# PICHeaderBoard.net
KiCad netlist of a schematic drawn in Altium Designer
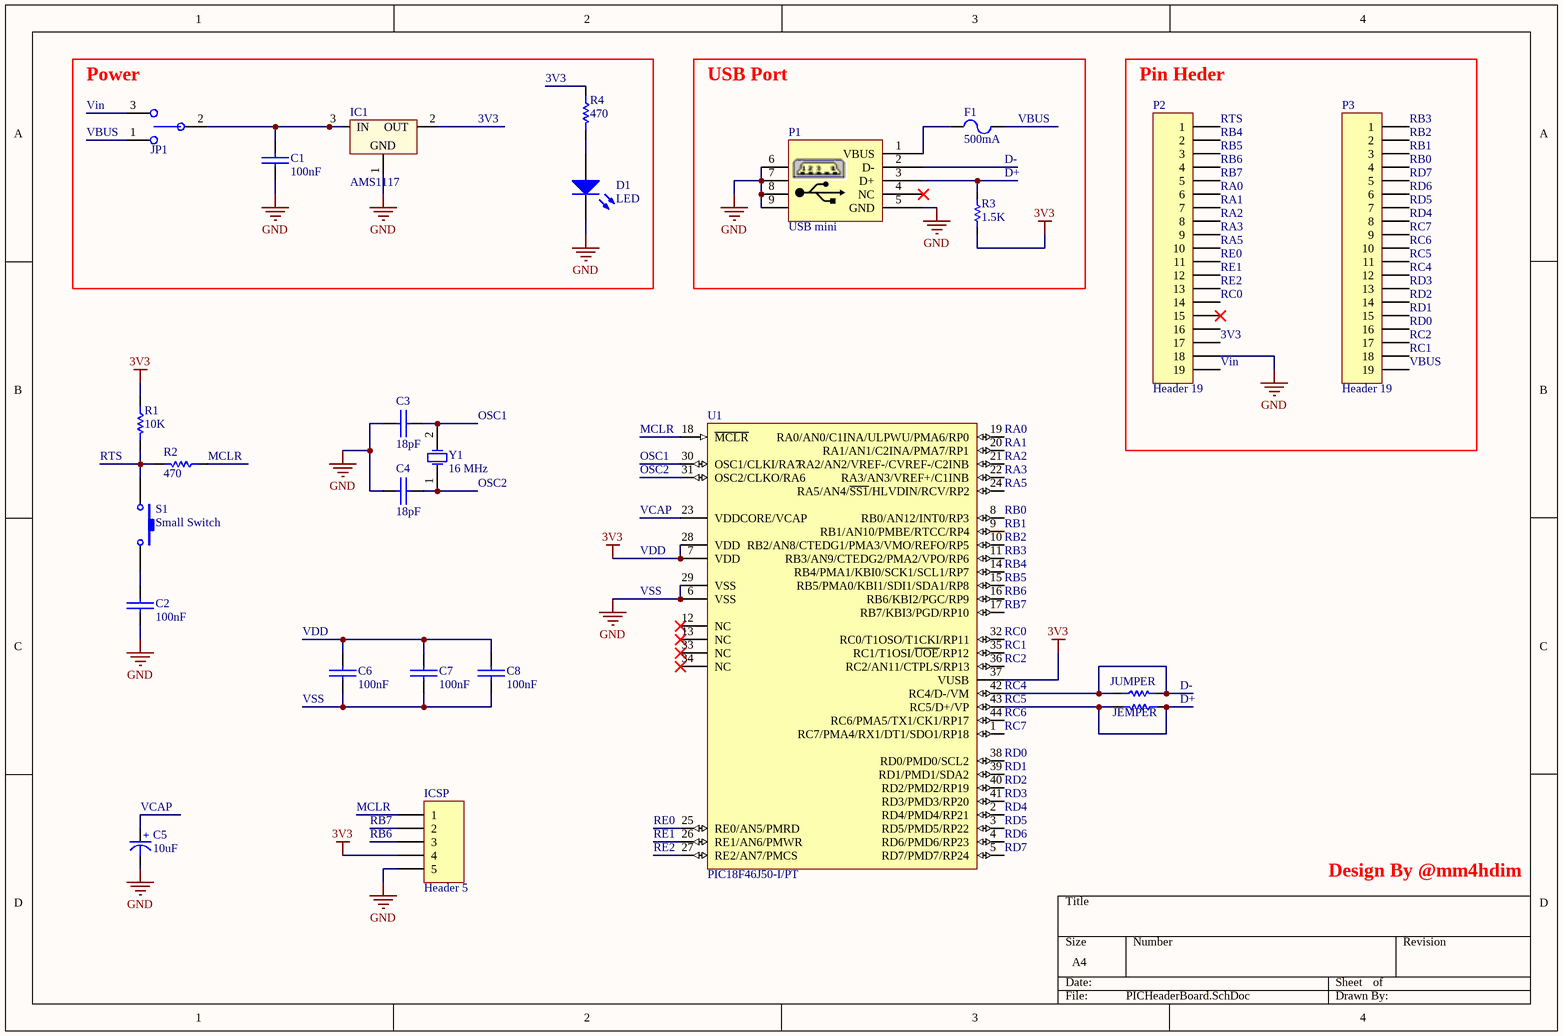
[diagram p0: PICHeaderBoard.SchDoc]

(export (version "E")
  (design (tool "Eeschema 10.0.6"))
  (components
    (comp (ref "C1")
      (value "100nF")
      (footprint "SMD_CAP_0805")
      (description "Bipolar Capacitor")
      (fields (field (name "VOLTAGE") "100V") (field (name "DESIGNER") "Saeid Jorablo"))
      (libsource (lib "My_Library") (part "Cap-Bipolar"))
    )
    (comp (ref "C2")
      (value "100nF")
      (footprint "SMD_CAP_0805")
      (description "Bipolar Capacitor")
      (fields (field (name "VOLTAGE") "100V") (field (name "DESIGNER") "Saeid Jorablo"))
      (libsource (lib "My_Library") (part "Cap-Bipolar"))
    )
    (comp (ref "C3")
      (value "18pF")
      (footprint "SMD_CAP_0805")
      (description "Bipolar Capacitor")
      (fields (field (name "VOLTAGE") "100V") (field (name "DESIGNER") "Saeid Jorablo"))
      (libsource (lib "My_Library") (part "Cap-Bipolar"))
    )
    (comp (ref "C4")
      (value "18pF")
      (footprint "SMD_CAP_0805")
      (description "Bipolar Capacitor")
      (fields (field (name "VOLTAGE") "100V") (field (name "DESIGNER") "Saeid Jorablo"))
      (libsource (lib "My_Library") (part "Cap-Bipolar"))
    )
    (comp (ref "C5")
      (value "10uF")
      (footprint "TANTAL-CAP-Size A")
      (description "Electrolytic Capacitor")
      (libsource (lib "AltiumLib1") (part "Capacitor Electrolytic"))
    )
    (comp (ref "C6")
      (value "100nF")
      (footprint "SMD_CAP_0805")
      (description "Bipolar Capacitor")
      (fields (field (name "VOLTAGE") "100V") (field (name "DESIGNER") "Saeid Jorablo"))
      (libsource (lib "My_Library") (part "Cap-Bipolar"))
    )
    (comp (ref "C7")
      (value "100nF")
      (footprint "SMD_CAP_0805")
      (description "Bipolar Capacitor")
      (fields (field (name "VOLTAGE") "100V") (field (name "DESIGNER") "Saeid Jorablo"))
      (libsource (lib "My_Library") (part "Cap-Bipolar"))
    )
    (comp (ref "C8")
      (value "100nF")
      (footprint "SMD_CAP_0805")
      (description "Bipolar Capacitor")
      (fields (field (name "VOLTAGE") "100V") (field (name "DESIGNER") "Saeid Jorablo"))
      (libsource (lib "My_Library") (part "Cap-Bipolar"))
    )
    (comp (ref "D1")
      (value "LED")
      (footprint "LED")
      (fields (field (name "PUBLISHER") "Altium Limited"))
      (libsource (lib "My Library") (part "LED"))
    )
    (comp (ref "F1")
      (value "500mA")
      (footprint "SMD_RES_1206")
      (description "Fuse")
      (libsource (lib "AltiumLib1") (part "Fuse"))
    )
    (comp (ref "IC1") (value "AMS1117") (footprint "SOT223") (libsource (lib "My Library") (part "AMS1117")))
    (comp (ref "ICSP")
      (value "Header 5")
      (footprint "HDR1X5")
      (description "Header, 5-Pin")
      (fields (field (name "PUBLISHER") "Altium Limited"))
      (libsource (lib "Miscellaneous Connectors") (part "Header 5"))
    )
    (comp (ref "J1")
      (value "JUMPER")
      (footprint "SMD_RES_0603")
      (description "Resistor")
      (fields (field (name "TOLERANCE") "5%") (field (name "POWER") "1/8 W"))
      (libsource (lib "My_Library") (part "Resistor"))
    )
    (comp (ref "J2")
      (value "JEMPER")
      (footprint "SMD_RES_0603")
      (description "Resistor")
      (fields (field (name "TOLERANCE") "5%") (field (name "POWER") "1/8 W"))
      (libsource (lib "My_Library") (part "Resistor"))
    )
    (comp (ref "JP1")
      (value "Jumper Selector")
      (footprint "Jumper Selector")
      (libsource (lib "AltiumLib1") (part "Jumper Selector"))
    )
    (comp (ref "P1")
      (value "USB mini")
      (footprint "USB/SM0.8-6H5")
      (description "mini USB Connector")
      (libsource (lib "My_Library") (part "USB mini"))
    )
    (comp (ref "P2")
      (value "Header 19")
      (footprint "HDR1X19")
      (description "Header, 19-Pin")
      (fields (field (name "PUBLISHER") "Altium Limited"))
      (libsource (lib "Miscellaneous Connectors") (part "Header 19"))
    )
    (comp (ref "P3")
      (value "Header 19")
      (footprint "HDR1X19")
      (description "Header, 19-Pin")
      (fields (field (name "PUBLISHER") "Altium Limited"))
      (libsource (lib "Miscellaneous Connectors") (part "Header 19"))
    )
    (comp (ref "R1")
      (value "10K")
      (footprint "SMD_RES_0805")
      (description "Resistor")
      (fields (field (name "TOLERANCE") "5%") (field (name "POWER") "1/8 W"))
      (libsource (lib "My_Library") (part "Resistor"))
    )
    (comp (ref "R2")
      (value "470")
      (footprint "SMD_RES_0805")
      (description "Resistor")
      (fields (field (name "TOLERANCE") "5%") (field (name "POWER") "1/8 W"))
      (libsource (lib "My_Library") (part "Resistor"))
    )
    (comp (ref "R3")
      (value "1.5K")
      (footprint "SMD_RES_0805")
      (description "Resistor")
      (fields (field (name "TOLERANCE") "5%") (field (name "POWER") "1/4 W"))
      (libsource (lib "AltiumLib1") (part "Resistor"))
    )
    (comp (ref "R4")
      (value "470")
      (footprint "SMD_RES_0805")
      (description "Resistor")
      (fields (field (name "TOLERANCE") "5%") (field (name "POWER") "1/8 W"))
      (libsource (lib "My_Library") (part "Resistor"))
    )
    (comp (ref "S1")
      (value "Small Switch")
      (footprint "Small Switch")
      (libsource (lib "My Library") (part "Small Switch"))
    )
    (comp (ref "U1")
      (value "PIC18F46J50-I/PT")
      (footprint "TQFP-PT44_N")
      (fields (field (name "PUBLISHER") "Altium Limited"))
      (libsource (lib "Microchip Microcontroller 8-Bit PIC18") (part "PIC18F46J50-I/PT"))
    )
    (comp (ref "Y1")
      (value "16 MHz")
      (footprint "XTAL Small")
      (description "XTAL Crystal")
      (libsource (lib "My_Library") (part "XTAL"))
    )
  )
  (nets
    (net (code "1") (name "/D+") (class "Default")
      (node (ref "J2") (pin "1") (pinfunction "1_1") (pintype "passive"))
      (node (ref "J2") (pin "2") (pinfunction "2_2") (pintype "passive"))
      (node (ref "P1") (pin "3") (pinfunction "D+_3") (pintype "passive"))
      (node (ref "P3") (pin "11") (pinfunction "11_11") (pintype "passive"))
      (node (ref "R3") (pin "2") (pinfunction "2_2") (pintype "passive"))
      (node (ref "U1") (pin "43") (pinfunction "RC5/D+/VP_43") (pintype "bidirectional"))
    )
    (net (code "2") (name "/D-") (class "Default")
      (node (ref "J1") (pin "1") (pinfunction "1_1") (pintype "passive"))
      (node (ref "J1") (pin "2") (pinfunction "2_2") (pintype "passive"))
      (node (ref "P1") (pin "2") (pinfunction "D-_2") (pintype "passive"))
      (node (ref "P3") (pin "12") (pinfunction "12_12") (pintype "passive"))
      (node (ref "U1") (pin "42") (pinfunction "RC4/D-/VM_42") (pintype "bidirectional"))
    )
    (net (code "3") (name "/MCLR") (class "Default")
      (node (ref "ICSP") (pin "1") (pinfunction "1_1") (pintype "passive"))
      (node (ref "R2") (pin "1") (pinfunction "1_1") (pintype "passive"))
      (node (ref "U1") (pin "18") (pinfunction "~{MCLR}_18") (pintype "input"))
    )
    (net (code "4") (name "/OSC1") (class "Default")
      (node (ref "C3") (pin "2") (pinfunction "-_2") (pintype "passive"))
      (node (ref "U1") (pin "30") (pinfunction "OSC1/CLKI/RA7_30") (pintype "bidirectional"))
      (node (ref "Y1") (pin "2") (pinfunction "OSC2_2") (pintype "passive"))
    )
    (net (code "5") (name "/OSC2") (class "Default")
      (node (ref "C4") (pin "2") (pinfunction "-_2") (pintype "passive"))
      (node (ref "U1") (pin "31") (pinfunction "OSC2/CLKO/RA6_31") (pintype "bidirectional"))
      (node (ref "Y1") (pin "1") (pinfunction "OSC1_1") (pintype "passive"))
    )
    (net (code "6") (name "/RA0") (class "Default")
      (node (ref "P2") (pin "6") (pinfunction "6_6") (pintype "passive"))
      (node (ref "U1") (pin "19") (pinfunction "RA0/AN0/C1INA/ULPWU/PMA6/RP0_19") (pintype "bidirectional"))
    )
    (net (code "7") (name "/RA1") (class "Default")
      (node (ref "P2") (pin "7") (pinfunction "7_7") (pintype "passive"))
      (node (ref "U1") (pin "20") (pinfunction "RA1/AN1/C2INA/PMA7/RP1_20") (pintype "bidirectional"))
    )
    (net (code "8") (name "/RA2") (class "Default")
      (node (ref "P2") (pin "8") (pinfunction "8_8") (pintype "passive"))
      (node (ref "U1") (pin "21") (pinfunction "RA2/AN2/VREF-/CVREF-/C2INB_21") (pintype "bidirectional"))
    )
    (net (code "9") (name "/RA3") (class "Default")
      (node (ref "P2") (pin "9") (pinfunction "9_9") (pintype "passive"))
      (node (ref "U1") (pin "22") (pinfunction "RA3/AN3/VREF+/C1INB_22") (pintype "bidirectional"))
    )
    (net (code "10") (name "/RA5") (class "Default")
      (node (ref "P2") (pin "10") (pinfunction "10_10") (pintype "passive"))
      (node (ref "U1") (pin "24") (pinfunction "RA5/AN4/~{SS1}/HLVDIN/RCV/RP2_24") (pintype "bidirectional"))
    )
    (net (code "11") (name "/RB0") (class "Default")
      (node (ref "P3") (pin "4") (pinfunction "4_4") (pintype "passive"))
      (node (ref "U1") (pin "8") (pinfunction "RB0/AN12/INT0/RP3_8") (pintype "bidirectional"))
    )
    (net (code "12") (name "/RB1") (class "Default")
      (node (ref "P3") (pin "3") (pinfunction "3_3") (pintype "passive"))
      (node (ref "U1") (pin "9") (pinfunction "RB1/AN10/PMBE/RTCC/RP4_9") (pintype "bidirectional"))
    )
    (net (code "13") (name "/RB2") (class "Default")
      (node (ref "P3") (pin "2") (pinfunction "2_2") (pintype "passive"))
      (node (ref "U1") (pin "10") (pinfunction "RB2/AN8/CTEDG1/PMA3/VMO/REFO/RP5_10") (pintype "bidirectional"))
    )
    (net (code "14") (name "/RB3") (class "Default")
      (node (ref "P3") (pin "1") (pinfunction "1_1") (pintype "passive"))
      (node (ref "U1") (pin "11") (pinfunction "RB3/AN9/CTEDG2/PMA2/VPO/RP6_11") (pintype "bidirectional"))
    )
    (net (code "15") (name "/RB4") (class "Default")
      (node (ref "P2") (pin "2") (pinfunction "2_2") (pintype "passive"))
      (node (ref "U1") (pin "14") (pinfunction "RB4/PMA1/KBI0/SCK1/SCL1/RP7_14") (pintype "bidirectional"))
    )
    (net (code "16") (name "/RB5") (class "Default")
      (node (ref "P2") (pin "3") (pinfunction "3_3") (pintype "passive"))
      (node (ref "U1") (pin "15") (pinfunction "RB5/PMA0/KBI1/SDI1/SDA1/RP8_15") (pintype "bidirectional"))
    )
    (net (code "17") (name "/RB6") (class "Default")
      (node (ref "ICSP") (pin "3") (pinfunction "3_3") (pintype "passive"))
      (node (ref "P2") (pin "4") (pinfunction "4_4") (pintype "passive"))
      (node (ref "U1") (pin "16") (pinfunction "RB6/KBI2/PGC/RP9_16") (pintype "bidirectional"))
    )
    (net (code "18") (name "/RB7") (class "Default")
      (node (ref "ICSP") (pin "2") (pinfunction "2_2") (pintype "passive"))
      (node (ref "P2") (pin "5") (pinfunction "5_5") (pintype "passive"))
      (node (ref "U1") (pin "17") (pinfunction "RB7/KBI3/PGD/RP10_17") (pintype "bidirectional"))
    )
    (net (code "19") (name "/RC0") (class "Default")
      (node (ref "P2") (pin "14") (pinfunction "14_14") (pintype "passive"))
      (node (ref "U1") (pin "32") (pinfunction "RC0/T1OSO/T1CKI/RP11_32") (pintype "bidirectional"))
    )
    (net (code "20") (name "/RC1") (class "Default")
      (node (ref "P3") (pin "18") (pinfunction "18_18") (pintype "passive"))
      (node (ref "U1") (pin "35") (pinfunction "RC1/T1OSI/~{UOE}/RP12_35") (pintype "bidirectional"))
    )
    (net (code "21") (name "/RC2") (class "Default")
      (node (ref "P3") (pin "17") (pinfunction "17_17") (pintype "passive"))
      (node (ref "U1") (pin "36") (pinfunction "RC2/AN11/CTPLS/RP13_36") (pintype "bidirectional"))
    )
    (net (code "22") (name "/RC6") (class "Default")
      (node (ref "P3") (pin "10") (pinfunction "10_10") (pintype "passive"))
      (node (ref "U1") (pin "44") (pinfunction "RC6/PMA5/TX1/CK1/RP17_44") (pintype "bidirectional"))
    )
    (net (code "23") (name "/RC7") (class "Default")
      (node (ref "P3") (pin "9") (pinfunction "9_9") (pintype "passive"))
      (node (ref "U1") (pin "1") (pinfunction "RC7/PMA4/RX1/DT1/SDO1/RP18_1") (pintype "bidirectional"))
    )
    (net (code "24") (name "/RD0") (class "Default")
      (node (ref "P3") (pin "16") (pinfunction "16_16") (pintype "passive"))
      (node (ref "U1") (pin "38") (pinfunction "RD0/PMD0/SCL2_38") (pintype "bidirectional"))
    )
    (net (code "25") (name "/RD1") (class "Default")
      (node (ref "P3") (pin "15") (pinfunction "15_15") (pintype "passive"))
      (node (ref "U1") (pin "39") (pinfunction "RD1/PMD1/SDA2_39") (pintype "bidirectional"))
    )
    (net (code "26") (name "/RD2") (class "Default")
      (node (ref "P3") (pin "14") (pinfunction "14_14") (pintype "passive"))
      (node (ref "U1") (pin "40") (pinfunction "RD2/PMD2/RP19_40") (pintype "bidirectional"))
    )
    (net (code "27") (name "/RD3") (class "Default")
      (node (ref "P3") (pin "13") (pinfunction "13_13") (pintype "passive"))
      (node (ref "U1") (pin "41") (pinfunction "RD3/PMD3/RP20_41") (pintype "bidirectional"))
    )
    (net (code "28") (name "/RD4") (class "Default")
      (node (ref "P3") (pin "8") (pinfunction "8_8") (pintype "passive"))
      (node (ref "U1") (pin "2") (pinfunction "RD4/PMD4/RP21_2") (pintype "bidirectional"))
    )
    (net (code "29") (name "/RD5") (class "Default")
      (node (ref "P3") (pin "7") (pinfunction "7_7") (pintype "passive"))
      (node (ref "U1") (pin "3") (pinfunction "RD5/PMD5/RP22_3") (pintype "bidirectional"))
    )
    (net (code "30") (name "/RD6") (class "Default")
      (node (ref "P3") (pin "6") (pinfunction "6_6") (pintype "passive"))
      (node (ref "U1") (pin "4") (pinfunction "RD6/PMD6/RP23_4") (pintype "bidirectional"))
    )
    (net (code "31") (name "/RD7") (class "Default")
      (node (ref "P3") (pin "5") (pinfunction "5_5") (pintype "passive"))
      (node (ref "U1") (pin "5") (pinfunction "RD7/PMD7/RP24_5") (pintype "bidirectional"))
    )
    (net (code "32") (name "/RE0") (class "Default")
      (node (ref "P2") (pin "11") (pinfunction "11_11") (pintype "passive"))
      (node (ref "U1") (pin "25") (pinfunction "RE0/AN5/PMRD_25") (pintype "bidirectional"))
    )
    (net (code "33") (name "/RE1") (class "Default")
      (node (ref "P2") (pin "12") (pinfunction "12_12") (pintype "passive"))
      (node (ref "U1") (pin "26") (pinfunction "RE1/AN6/PMWR_26") (pintype "bidirectional"))
    )
    (net (code "34") (name "/RE2") (class "Default")
      (node (ref "P2") (pin "13") (pinfunction "13_13") (pintype "passive"))
      (node (ref "U1") (pin "27") (pinfunction "RE2/AN7/PMCS_27") (pintype "bidirectional"))
    )
    (net (code "35") (name "/RTS") (class "Default")
      (node (ref "P2") (pin "1") (pinfunction "1_1") (pintype "passive"))
      (node (ref "R1") (pin "2") (pinfunction "2_2") (pintype "passive"))
      (node (ref "R2") (pin "2") (pinfunction "2_2") (pintype "passive"))
      (node (ref "S1") (pin "1") (pinfunction "1_1") (pintype "passive"))
    )
    (net (code "36") (name "/VBUS") (class "Default")
      (node (ref "F1") (pin "2") (pinfunction "2_2") (pintype "passive"))
      (node (ref "JP1") (pin "1") (pinfunction "1_1") (pintype "passive"))
      (node (ref "P3") (pin "19") (pinfunction "19_19") (pintype "passive"))
    )
    (net (code "37") (name "/VCAP") (class "Default")
      (node (ref "C5") (pin "2") (pinfunction "+_2") (pintype "passive"))
      (node (ref "U1") (pin "23") (pinfunction "VDDCORE/VCAP_23") (pintype "power_in"))
    )
    (net (code "38") (name "/Vin") (class "Default")
      (node (ref "JP1") (pin "3") (pinfunction "3_3") (pintype "passive"))
      (node (ref "P2") (pin "19") (pinfunction "19_19") (pintype "passive"))
    )
    (net (code "39") (name "3V3") (class "Default")
      (node (ref "C6") (pin "1") (pinfunction "+_1") (pintype "passive"))
      (node (ref "C7") (pin "1") (pinfunction "+_1") (pintype "passive"))
      (node (ref "C8") (pin "1") (pinfunction "+_1") (pintype "passive"))
      (node (ref "IC1") (pin "2") (pinfunction "OUT_2") (pintype "power_in"))
      (node (ref "ICSP") (pin "4") (pinfunction "4_4") (pintype "passive"))
      (node (ref "P2") (pin "17") (pinfunction "17_17") (pintype "passive"))
      (node (ref "R1") (pin "1") (pinfunction "1_1") (pintype "passive"))
      (node (ref "R3") (pin "1") (pinfunction "1_1") (pintype "passive"))
      (node (ref "R4") (pin "1") (pinfunction "1_1") (pintype "passive"))
      (node (ref "U1") (pin "28") (pinfunction "VDD_28") (pintype "power_in"))
      (node (ref "U1") (pin "37") (pinfunction "VUSB_37") (pintype "power_in"))
      (node (ref "U1") (pin "7") (pinfunction "VDD_7") (pintype "power_in"))
    )
    (net (code "40") (name "GND") (class "Default")
      (node (ref "C1") (pin "2") (pinfunction "-_2") (pintype "passive"))
      (node (ref "C2") (pin "2") (pinfunction "-_2") (pintype "passive"))
      (node (ref "C3") (pin "1") (pinfunction "+_1") (pintype "passive"))
      (node (ref "C4") (pin "1") (pinfunction "+_1") (pintype "passive"))
      (node (ref "C5") (pin "1") (pinfunction "-_1") (pintype "passive"))
      (node (ref "C6") (pin "2") (pinfunction "-_2") (pintype "passive"))
      (node (ref "C7") (pin "2") (pinfunction "-_2") (pintype "passive"))
      (node (ref "C8") (pin "2") (pinfunction "-_2") (pintype "passive"))
      (node (ref "D1") (pin "2") (pinfunction "K_2") (pintype "passive"))
      (node (ref "IC1") (pin "1") (pinfunction "GND_1") (pintype "power_in"))
      (node (ref "ICSP") (pin "5") (pinfunction "5_5") (pintype "passive"))
      (node (ref "P1") (pin "5") (pinfunction "GND_5") (pintype "power_in"))
      (node (ref "P1") (pin "6") (pinfunction "6_6") (pintype "passive"))
      (node (ref "P1") (pin "7") (pinfunction "7_7") (pintype "passive"))
      (node (ref "P1") (pin "8") (pinfunction "8_8") (pintype "passive"))
      (node (ref "P1") (pin "9") (pinfunction "9_9") (pintype "passive"))
      (node (ref "P2") (pin "18") (pinfunction "18_18") (pintype "passive"))
      (node (ref "U1") (pin "29") (pinfunction "VSS_29") (pintype "power_in"))
      (node (ref "U1") (pin "6") (pinfunction "VSS_6") (pintype "power_in"))
    )
    (net (code "41") (name "Net-(C1-+)") (class "Default")
      (node (ref "C1") (pin "1") (pinfunction "+_1") (pintype "passive"))
      (node (ref "IC1") (pin "3") (pinfunction "IN_3") (pintype "power_in"))
      (node (ref "JP1") (pin "2") (pinfunction "2_2") (pintype "passive"))
    )
    (net (code "42") (name "Net-(C2-+)") (class "Default")
      (node (ref "C2") (pin "1") (pinfunction "+_1") (pintype "passive"))
      (node (ref "S1") (pin "2") (pinfunction "2_2") (pintype "passive"))
    )
    (net (code "43") (name "Net-(D1-A)") (class "Default")
      (node (ref "D1") (pin "1") (pinfunction "A_1") (pintype "passive"))
      (node (ref "R4") (pin "2") (pinfunction "2_2") (pintype "passive"))
    )
    (net (code "44") (name "Net-(P1-VBUS)") (class "Default")
      (node (ref "F1") (pin "1") (pinfunction "1_1") (pintype "passive"))
      (node (ref "P1") (pin "1") (pinfunction "VBUS_1") (pintype "power_in"))
    )
    (net (code "45") (name "unconnected-(P1-NC-Pad4)") (class "Default")
      (node (ref "P1") (pin "4") (pinfunction "NC_4") (pintype "power_in+no_connect"))
    )
    (net (code "46") (name "unconnected-(P2-Pad15)") (class "Default")
      (node (ref "P2") (pin "15") (pinfunction "15_15") (pintype "passive+no_connect"))
    )
    (net (code "47") (name "unconnected-(P2-Pad16)") (class "Default")
      (node (ref "P2") (pin "16") (pinfunction "16_16") (pintype "passive"))
    )
    (net (code "48") (name "unconnected-(U1-NC-Pad12)") (class "Default")
      (node (ref "U1") (pin "12") (pinfunction "NC_12") (pintype "passive+no_connect"))
    )
    (net (code "49") (name "unconnected-(U1-NC-Pad13)") (class "Default")
      (node (ref "U1") (pin "13") (pinfunction "NC_13") (pintype "passive+no_connect"))
    )
    (net (code "50") (name "unconnected-(U1-NC-Pad33)") (class "Default")
      (node (ref "U1") (pin "33") (pinfunction "NC_33") (pintype "passive+no_connect"))
    )
    (net (code "51") (name "unconnected-(U1-NC-Pad34)") (class "Default")
      (node (ref "U1") (pin "34") (pinfunction "NC_34") (pintype "passive+no_connect"))
    )
  )
)
